# USB_Headers.net
KiCad netlist of a schematic drawn in Altium Designer
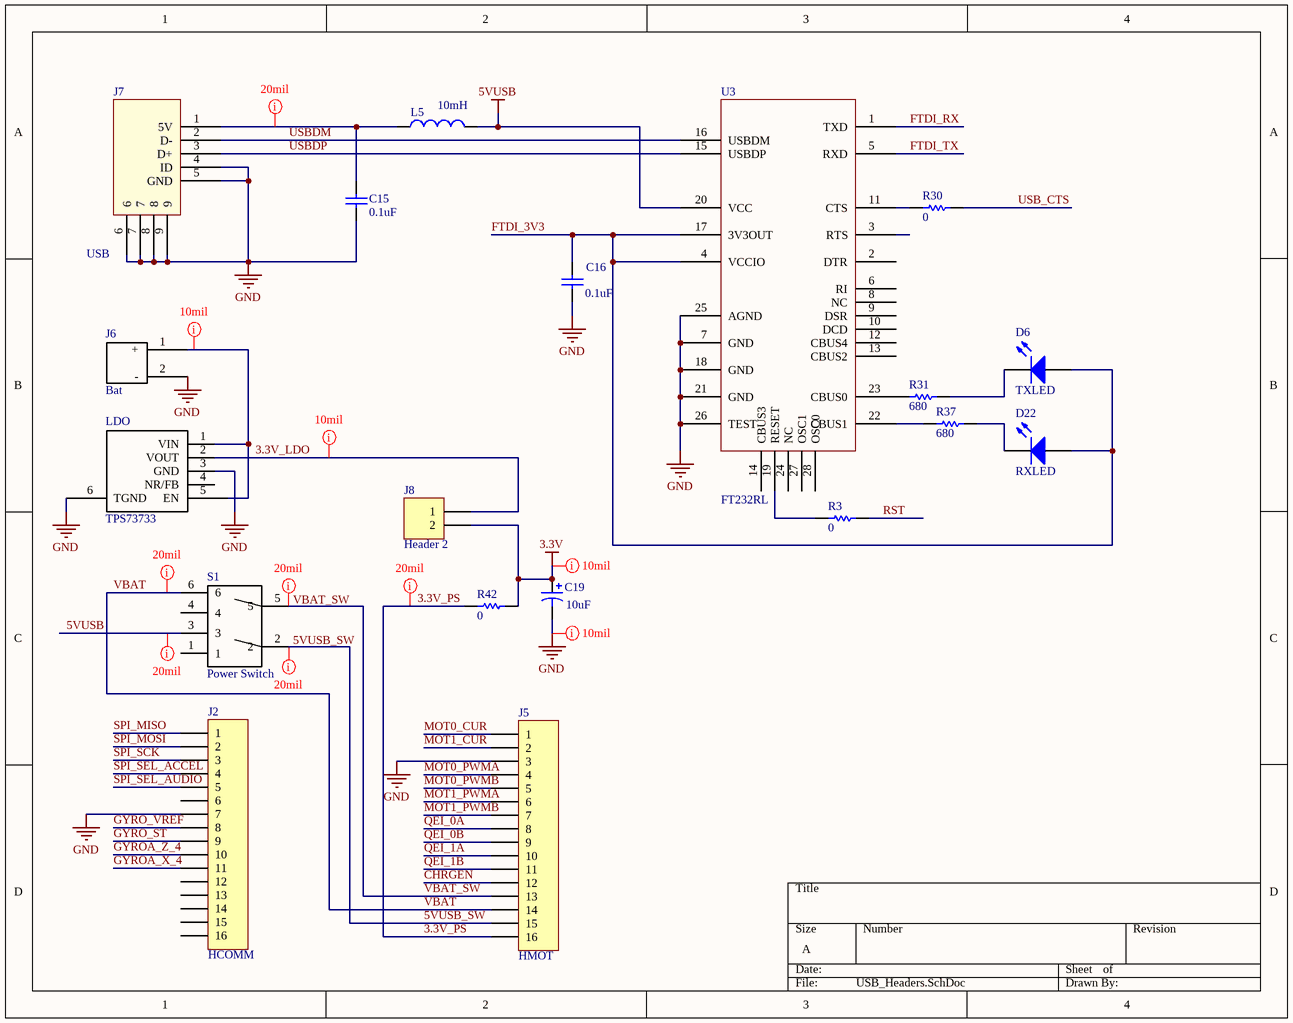
[diagram p0: USB_Headers.SchDoc]

(export (version "E")
  (design (tool "Eeschema 10.0.6"))
  (components
    (comp (ref "C15")
      (value "0.1uF")
      (footprint "CAPC1005L")
      (description "Capacitor")
      (fields (field (name "PUBLISHER") "Altium Limited"))
      (libsource (lib "Miscellaneous Devices") (part "Cap"))
    )
    (comp (ref "C16")
      (value "0.1uF")
      (footprint "CAPC1005L")
      (description "Capacitor")
      (fields (field (name "PUBLISHER") "Altium Limited"))
      (libsource (lib "Miscellaneous Devices") (part "Cap"))
    )
    (comp (ref "C19")
      (value "10uF")
      (footprint "CAPC3216L")
      (description "Polarized Capacitor (Surface Mount)")
      (fields (field (name "Comment") "Cap Pol3") (field (name "PUBLISHER") "Altium Limited"))
      (libsource (lib "Miscellaneous Devices") (part "Cap Pol3"))
    )
    (comp (ref "D6")
      (value "TXLED")
      (footprint "INDC2012L")
      (description "Typical RED, GREEN, YELLOW, AMBER GaAs LED")
      (fields (field (name "PUBLISHER") "Altium Limited"))
      (libsource (lib "Miscellaneous Devices") (part "LED2"))
    )
    (comp (ref "D22")
      (value "RXLED")
      (footprint "INDC2012L")
      (description "Typical RED, GREEN, YELLOW, AMBER GaAs LED")
      (fields (field (name "PUBLISHER") "Altium Limited"))
      (libsource (lib "Miscellaneous Devices") (part "LED2"))
    )
    (comp (ref "J2")
      (value "HCOMM")
      (footprint "HDR1X16")
      (description "Header, 16-Pin")
      (fields (field (name "PUBLISHER") "Altium Limited"))
      (libsource (lib "Miscellaneous Connectors") (part "Header 16"))
    )
    (comp (ref "J5")
      (value "HMOT")
      (footprint "HDR1X16")
      (description "Header, 16-Pin")
      (fields (field (name "PUBLISHER") "Altium Limited"))
      (libsource (lib "Miscellaneous Connectors") (part "Header 16"))
    )
    (comp (ref "J6")
      (value "Bat")
      (footprint "BatteryConnJST")
      (libsource (lib "mrone") (part "BatteryConnJST"))
    )
    (comp (ref "J7")
      (value "USB")
      (footprint "USB Minib (thru-hole)")
      (libsource (lib "mrone") (part "USB-ConnTH"))
    )
    (comp (ref "J8")
      (value "Header 2")
      (footprint "HDR1X2")
      (description "Header, 2-Pin")
      (fields (field (name "PUBLISHER") "Altium Limited"))
      (libsource (lib "Miscellaneous Connectors") (part "Header 2"))
    )
    (comp (ref "L5")
      (value "10mH")
      (footprint "INDC2012L")
      (description "Inductor")
      (fields (field (name "PUBLISHER") "Altium Limited"))
      (libsource (lib "Miscellaneous Devices") (part "Inductor"))
    )
    (comp (ref "LDO")
      (value "TPS73733")
      (footprint "SOT-223-5pin")
      (libsource (lib "mrone") (part "LDO33-TI-TPS73733"))
    )
    (comp (ref "R3")
      (value "0")
      (footprint "RESC1608L")
      (description "Resistor")
      (fields (field (name "PUBLISHER") "Altium Limited"))
      (libsource (lib "Miscellaneous Devices") (part "Res1"))
    )
    (comp (ref "R30")
      (value "0")
      (footprint "RESC1608L")
      (description "Resistor")
      (fields (field (name "PUBLISHER") "Altium Limited"))
      (libsource (lib "Miscellaneous Devices") (part "Res1"))
    )
    (comp (ref "R31")
      (value "680")
      (footprint "RESC1608L")
      (description "Resistor")
      (fields (field (name "PUBLISHER") "Altium Limited"))
      (libsource (lib "Miscellaneous Devices") (part "Res1"))
    )
    (comp (ref "R37")
      (value "680")
      (footprint "RESC1608L")
      (description "Resistor")
      (fields (field (name "PUBLISHER") "Altium Limited"))
      (libsource (lib "Miscellaneous Devices") (part "Res1"))
    )
    (comp (ref "R42")
      (value "0")
      (footprint "RESC3216L")
      (description "Resistor")
      (fields (field (name "PUBLISHER") "Altium Limited"))
      (libsource (lib "Miscellaneous Devices") (part "Res1"))
    )
    (comp (ref "S1")
      (value "Power Switch")
      (footprint "DPDTSwitch")
      (libsource (lib "mrone") (part "DPDTSwitch"))
    )
    (comp (ref "U3") (value "FT232RL") (footprint "SSOP-28") (libsource (lib "mrone") (part "FT232RL")))
  )
  (nets
    (net (code "1") (name "/3.3V_LDO") (class "Default")
      (node (ref "J8") (pin "1") (pinfunction "1_1") (pintype "passive"))
      (node (ref "LDO") (pin "2") (pinfunction "VOUT_2") (pintype "passive"))
    )
    (net (code "2") (name "/3.3V_PS") (class "Default")
      (node (ref "J5") (pin "16") (pinfunction "16_16") (pintype "passive"))
      (node (ref "R42") (pin "1") (pinfunction "1_1") (pintype "passive"))
    )
    (net (code "3") (name "/5VUSB_SW") (class "Default")
      (node (ref "J5") (pin "15") (pinfunction "15_15") (pintype "passive"))
      (node (ref "S1") (pin "2") (pinfunction "2_2") (pintype "passive"))
    )
    (net (code "4") (name "/CHRGEN") (class "Default")
      (node (ref "J5") (pin "12") (pinfunction "12_12") (pintype "passive"))
    )
    (net (code "5") (name "/FTDI_3V3") (class "Default")
      (node (ref "C16") (pin "2") (pinfunction "2_2") (pintype "passive"))
      (node (ref "D22") (pin "1") (pinfunction "A_1") (pintype "passive"))
      (node (ref "D6") (pin "1") (pinfunction "A_1") (pintype "passive"))
      (node (ref "U3") (pin "17") (pinfunction "3V3OUT_17") (pintype "passive"))
      (node (ref "U3") (pin "4") (pinfunction "VCCIO_4") (pintype "passive"))
    )
    (net (code "6") (name "/FTDI_RX") (class "Default")
      (node (ref "U3") (pin "1") (pinfunction "TXD_1") (pintype "passive"))
    )
    (net (code "7") (name "/FTDI_TX") (class "Default")
      (node (ref "U3") (pin "5") (pinfunction "RXD_5") (pintype "passive"))
    )
    (net (code "8") (name "/GYROA_X_4") (class "Default")
      (node (ref "J2") (pin "11") (pinfunction "11_11") (pintype "passive"))
    )
    (net (code "9") (name "/GYROA_Z_4") (class "Default")
      (node (ref "J2") (pin "10") (pinfunction "10_10") (pintype "passive"))
    )
    (net (code "10") (name "/GYRO_ST") (class "Default")
      (node (ref "J2") (pin "9") (pinfunction "9_9") (pintype "passive"))
    )
    (net (code "11") (name "/GYRO_VREF") (class "Default")
      (node (ref "J2") (pin "8") (pinfunction "8_8") (pintype "passive"))
    )
    (net (code "12") (name "/MOT0_CUR") (class "Default")
      (node (ref "J5") (pin "1") (pinfunction "1_1") (pintype "passive"))
    )
    (net (code "13") (name "/MOT0_PWMA") (class "Default")
      (node (ref "J5") (pin "4") (pinfunction "4_4") (pintype "passive"))
    )
    (net (code "14") (name "/MOT0_PWMB") (class "Default")
      (node (ref "J5") (pin "5") (pinfunction "5_5") (pintype "passive"))
    )
    (net (code "15") (name "/MOT1_CUR") (class "Default")
      (node (ref "J5") (pin "2") (pinfunction "2_2") (pintype "passive"))
    )
    (net (code "16") (name "/MOT1_PWMA") (class "Default")
      (node (ref "J5") (pin "6") (pinfunction "6_6") (pintype "passive"))
    )
    (net (code "17") (name "/MOT1_PWMB") (class "Default")
      (node (ref "J5") (pin "7") (pinfunction "7_7") (pintype "passive"))
    )
    (net (code "18") (name "/QEI_0A") (class "Default")
      (node (ref "J5") (pin "8") (pinfunction "8_8") (pintype "passive"))
    )
    (net (code "19") (name "/QEI_0B") (class "Default")
      (node (ref "J5") (pin "9") (pinfunction "9_9") (pintype "passive"))
    )
    (net (code "20") (name "/QEI_1A") (class "Default")
      (node (ref "J5") (pin "10") (pinfunction "10_10") (pintype "passive"))
    )
    (net (code "21") (name "/QEI_1B") (class "Default")
      (node (ref "J5") (pin "11") (pinfunction "11_11") (pintype "passive"))
    )
    (net (code "22") (name "/RST") (class "Default")
      (node (ref "R3") (pin "2") (pinfunction "2_2") (pintype "passive"))
    )
    (net (code "23") (name "/SPI_MISO") (class "Default")
      (node (ref "J2") (pin "1") (pinfunction "1_1") (pintype "passive"))
    )
    (net (code "24") (name "/SPI_MOSI") (class "Default")
      (node (ref "J2") (pin "2") (pinfunction "2_2") (pintype "passive"))
    )
    (net (code "25") (name "/SPI_SCK") (class "Default")
      (node (ref "J2") (pin "3") (pinfunction "3_3") (pintype "passive"))
    )
    (net (code "26") (name "/SPI_SEL_ACCEL") (class "Default")
      (node (ref "J2") (pin "4") (pinfunction "4_4") (pintype "passive"))
    )
    (net (code "27") (name "/SPI_SEL_AUDIO") (class "Default")
      (node (ref "J2") (pin "5") (pinfunction "5_5") (pintype "passive"))
    )
    (net (code "28") (name "/USBDM") (class "Default")
      (node (ref "J7") (pin "2") (pinfunction "D-_2") (pintype "passive"))
      (node (ref "U3") (pin "16") (pinfunction "USBDM_16") (pintype "passive"))
    )
    (net (code "29") (name "/USBDP") (class "Default")
      (node (ref "J7") (pin "3") (pinfunction "D+_3") (pintype "passive"))
      (node (ref "U3") (pin "15") (pinfunction "USBDP_15") (pintype "passive"))
    )
    (net (code "30") (name "/USB_CTS") (class "Default")
      (node (ref "R30") (pin "2") (pinfunction "2_2") (pintype "passive"))
    )
    (net (code "31") (name "/VBAT") (class "Default")
      (node (ref "J5") (pin "14") (pinfunction "14_14") (pintype "passive"))
      (node (ref "S1") (pin "6") (pinfunction "6_6") (pintype "passive"))
    )
    (net (code "32") (name "/VBAT_SW") (class "Default")
      (node (ref "J5") (pin "13") (pinfunction "13_13") (pintype "passive"))
      (node (ref "S1") (pin "5") (pinfunction "5_5") (pintype "passive"))
    )
    (net (code "33") (name "3.3V") (class "Default")
      (node (ref "C19") (pin "1") (pinfunction "1_1") (pintype "passive"))
      (node (ref "J8") (pin "2") (pinfunction "2_2") (pintype "passive"))
      (node (ref "R42") (pin "2") (pinfunction "2_2") (pintype "passive"))
    )
    (net (code "34") (name "5VUSB") (class "Default")
      (node (ref "L5") (pin "2") (pinfunction "2_2") (pintype "passive"))
      (node (ref "S1") (pin "3") (pinfunction "3_3") (pintype "passive"))
      (node (ref "U3") (pin "20") (pinfunction "VCC_20") (pintype "passive"))
    )
    (net (code "35") (name "GND") (class "Default")
      (node (ref "C15") (pin "1") (pinfunction "1_1") (pintype "passive"))
      (node (ref "C16") (pin "1") (pinfunction "1_1") (pintype "passive"))
      (node (ref "C19") (pin "2") (pinfunction "2_2") (pintype "passive"))
      (node (ref "J2") (pin "7") (pinfunction "7_7") (pintype "passive"))
      (node (ref "J5") (pin "3") (pinfunction "3_3") (pintype "passive"))
      (node (ref "J6") (pin "2") (pinfunction "-_2") (pintype "passive"))
      (node (ref "J7") (pin "4") (pinfunction "ID_4") (pintype "passive"))
      (node (ref "J7") (pin "5") (pinfunction "GND_5") (pintype "passive"))
      (node (ref "J7") (pin "6") (pinfunction "6_6") (pintype "passive"))
      (node (ref "J7") (pin "7") (pinfunction "7_7") (pintype "passive"))
      (node (ref "J7") (pin "8") (pinfunction "8_8") (pintype "passive"))
      (node (ref "J7") (pin "9") (pinfunction "9_9") (pintype "passive"))
      (node (ref "LDO") (pin "3") (pinfunction "GND_3") (pintype "passive"))
      (node (ref "LDO") (pin "6") (pinfunction "TGND_6") (pintype "passive"))
      (node (ref "U3") (pin "18") (pinfunction "GND_18") (pintype "passive"))
      (node (ref "U3") (pin "21") (pinfunction "GND_21") (pintype "passive"))
      (node (ref "U3") (pin "25") (pinfunction "AGND_25") (pintype "passive"))
      (node (ref "U3") (pin "26") (pinfunction "TEST_26") (pintype "passive"))
      (node (ref "U3") (pin "7") (pinfunction "GND_7") (pintype "passive"))
    )
    (net (code "36") (name "Net-(D6-K)") (class "Default")
      (node (ref "D6") (pin "2") (pinfunction "K_2") (pintype "passive"))
      (node (ref "R31") (pin "2") (pinfunction "2_2") (pintype "passive"))
    )
    (net (code "37") (name "Net-(D22-K)") (class "Default")
      (node (ref "D22") (pin "2") (pinfunction "K_2") (pintype "passive"))
      (node (ref "R37") (pin "2") (pinfunction "2_2") (pintype "passive"))
    )
    (net (code "38") (name "Net-(J6-+)") (class "Default")
      (node (ref "J6") (pin "1") (pinfunction "+_1") (pintype "passive"))
      (node (ref "LDO") (pin "1") (pinfunction "VIN_1") (pintype "passive"))
      (node (ref "LDO") (pin "5") (pinfunction "EN_5") (pintype "passive"))
    )
    (net (code "39") (name "Net-(J7-5V)") (class "Default")
      (node (ref "C15") (pin "2") (pinfunction "2_2") (pintype "passive"))
      (node (ref "J7") (pin "1") (pinfunction "5V_1") (pintype "passive"))
      (node (ref "L5") (pin "1") (pinfunction "1_1") (pintype "passive"))
    )
    (net (code "40") (name "Net-(U3-CBUS0)") (class "Default")
      (node (ref "R31") (pin "1") (pinfunction "1_1") (pintype "passive"))
      (node (ref "U3") (pin "23") (pinfunction "CBUS0_23") (pintype "passive"))
    )
    (net (code "41") (name "Net-(U3-CBUS1)") (class "Default")
      (node (ref "R37") (pin "1") (pinfunction "1_1") (pintype "passive"))
      (node (ref "U3") (pin "22") (pinfunction "CBUS1_22") (pintype "passive"))
    )
    (net (code "42") (name "Net-(U3-CTS)") (class "Default")
      (node (ref "R30") (pin "1") (pinfunction "1_1") (pintype "passive"))
      (node (ref "U3") (pin "11") (pinfunction "CTS_11") (pintype "passive"))
    )
    (net (code "43") (name "Net-(U3-RESET)") (class "Default")
      (node (ref "R3") (pin "1") (pinfunction "1_1") (pintype "passive"))
      (node (ref "U3") (pin "19") (pinfunction "RESET_19") (pintype "passive"))
    )
    (net (code "44") (name "unconnected-(J2-Pad6)") (class "Default")
      (node (ref "J2") (pin "6") (pinfunction "6_6") (pintype "passive"))
    )
    (net (code "45") (name "unconnected-(J2-Pad12)") (class "Default")
      (node (ref "J2") (pin "12") (pinfunction "12_12") (pintype "passive"))
    )
    (net (code "46") (name "unconnected-(J2-Pad13)") (class "Default")
      (node (ref "J2") (pin "13") (pinfunction "13_13") (pintype "passive"))
    )
    (net (code "47") (name "unconnected-(J2-Pad14)") (class "Default")
      (node (ref "J2") (pin "14") (pinfunction "14_14") (pintype "passive"))
    )
    (net (code "48") (name "unconnected-(J2-Pad15)") (class "Default")
      (node (ref "J2") (pin "15") (pinfunction "15_15") (pintype "passive"))
    )
    (net (code "49") (name "unconnected-(J2-Pad16)") (class "Default")
      (node (ref "J2") (pin "16") (pinfunction "16_16") (pintype "passive"))
    )
    (net (code "50") (name "unconnected-(LDO-NR{slash}FB-Pad4)") (class "Default")
      (node (ref "LDO") (pin "4") (pinfunction "NR/FB_4") (pintype "passive"))
    )
    (net (code "51") (name "unconnected-(S1-Pad1)") (class "Default")
      (node (ref "S1") (pin "1") (pinfunction "1_1") (pintype "passive"))
    )
    (net (code "52") (name "unconnected-(S1-Pad4)") (class "Default")
      (node (ref "S1") (pin "4") (pinfunction "4_4") (pintype "passive"))
    )
    (net (code "53") (name "unconnected-(U3-CBUS2-Pad13)") (class "Default")
      (node (ref "U3") (pin "13") (pinfunction "CBUS2_13") (pintype "passive"))
    )
    (net (code "54") (name "unconnected-(U3-CBUS3-Pad14)") (class "Default")
      (node (ref "U3") (pin "14") (pinfunction "CBUS3_14") (pintype "passive"))
    )
    (net (code "55") (name "unconnected-(U3-CBUS4-Pad12)") (class "Default")
      (node (ref "U3") (pin "12") (pinfunction "CBUS4_12") (pintype "passive"))
    )
    (net (code "56") (name "unconnected-(U3-DCD-Pad10)") (class "Default")
      (node (ref "U3") (pin "10") (pinfunction "DCD_10") (pintype "passive"))
    )
    (net (code "57") (name "unconnected-(U3-DSR-Pad9)") (class "Default")
      (node (ref "U3") (pin "9") (pinfunction "DSR_9") (pintype "passive"))
    )
    (net (code "58") (name "unconnected-(U3-DTR-Pad2)") (class "Default")
      (node (ref "U3") (pin "2") (pinfunction "DTR_2") (pintype "passive"))
    )
    (net (code "59") (name "unconnected-(U3-NC-Pad8)") (class "Default")
      (node (ref "U3") (pin "8") (pinfunction "NC_8") (pintype "passive"))
    )
    (net (code "60") (name "unconnected-(U3-NC-Pad24)") (class "Default")
      (node (ref "U3") (pin "24") (pinfunction "NC_24") (pintype "passive"))
    )
    (net (code "61") (name "unconnected-(U3-OSC0-Pad28)") (class "Default")
      (node (ref "U3") (pin "28") (pinfunction "OSC0_28") (pintype "passive"))
    )
    (net (code "62") (name "unconnected-(U3-OSC1-Pad27)") (class "Default")
      (node (ref "U3") (pin "27") (pinfunction "OSC1_27") (pintype "passive"))
    )
    (net (code "63") (name "unconnected-(U3-RI-Pad6)") (class "Default")
      (node (ref "U3") (pin "6") (pinfunction "RI_6") (pintype "passive"))
    )
    (net (code "64") (name "unconnected-(U3-RTS-Pad3)") (class "Default")
      (node (ref "U3") (pin "3") (pinfunction "RTS_3") (pintype "passive"))
    )
  )
)
